# temp_sensor_board.net
KiCad netlist of a schematic drawn in Altium Designer
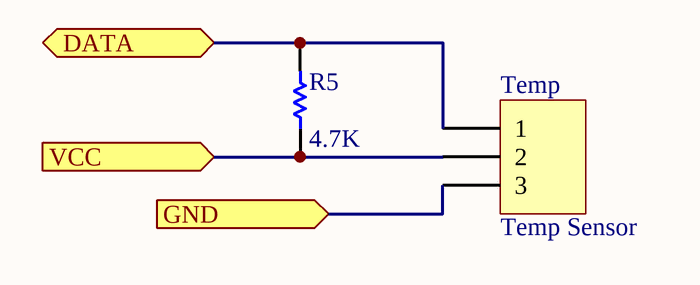
[diagram p0: temp_sensor_board.SchDoc]

(export (version "E")
  (design (tool "Eeschema 10.0.6"))
  (components
    (comp (ref "R5")
      (value "4.7K")
      (footprint "AXIAL-0.3")
      (description "Pull up")
      (fields (field (name "PUBLISHER") "Altium Limited"))
      (libsource (lib "Miscellaneous Devices") (part "Res1"))
    )
    (comp (ref "Temp")
      (value "Temp Sensor")
      (footprint "HDR1X3")
      (description "Header, 3-Pin")
      (fields (field (name "PUBLISHER") "Altium Limited"))
      (libsource (lib "altium-import") (part "root_0_Header 3_"))
    )
  )
  (nets
    (net (code "1") (name "/DATA") (class "Default")
      (node (ref "R5") (pin "2") (pinfunction "2_2") (pintype "passive"))
      (node (ref "Temp") (pin "1") (pinfunction "1_1") (pintype "passive"))
    )
    (net (code "2") (name "/GND") (class "Default")
      (node (ref "Temp") (pin "3") (pinfunction "3_3") (pintype "passive"))
    )
    (net (code "3") (name "/VCC") (class "Default")
      (node (ref "R5") (pin "1") (pinfunction "1_1") (pintype "passive"))
      (node (ref "Temp") (pin "2") (pinfunction "2_2") (pintype "passive"))
    )
  )
)
